# VA-Meter_Power_Supply.net
KiCad netlist of a schematic drawn in EAGLE
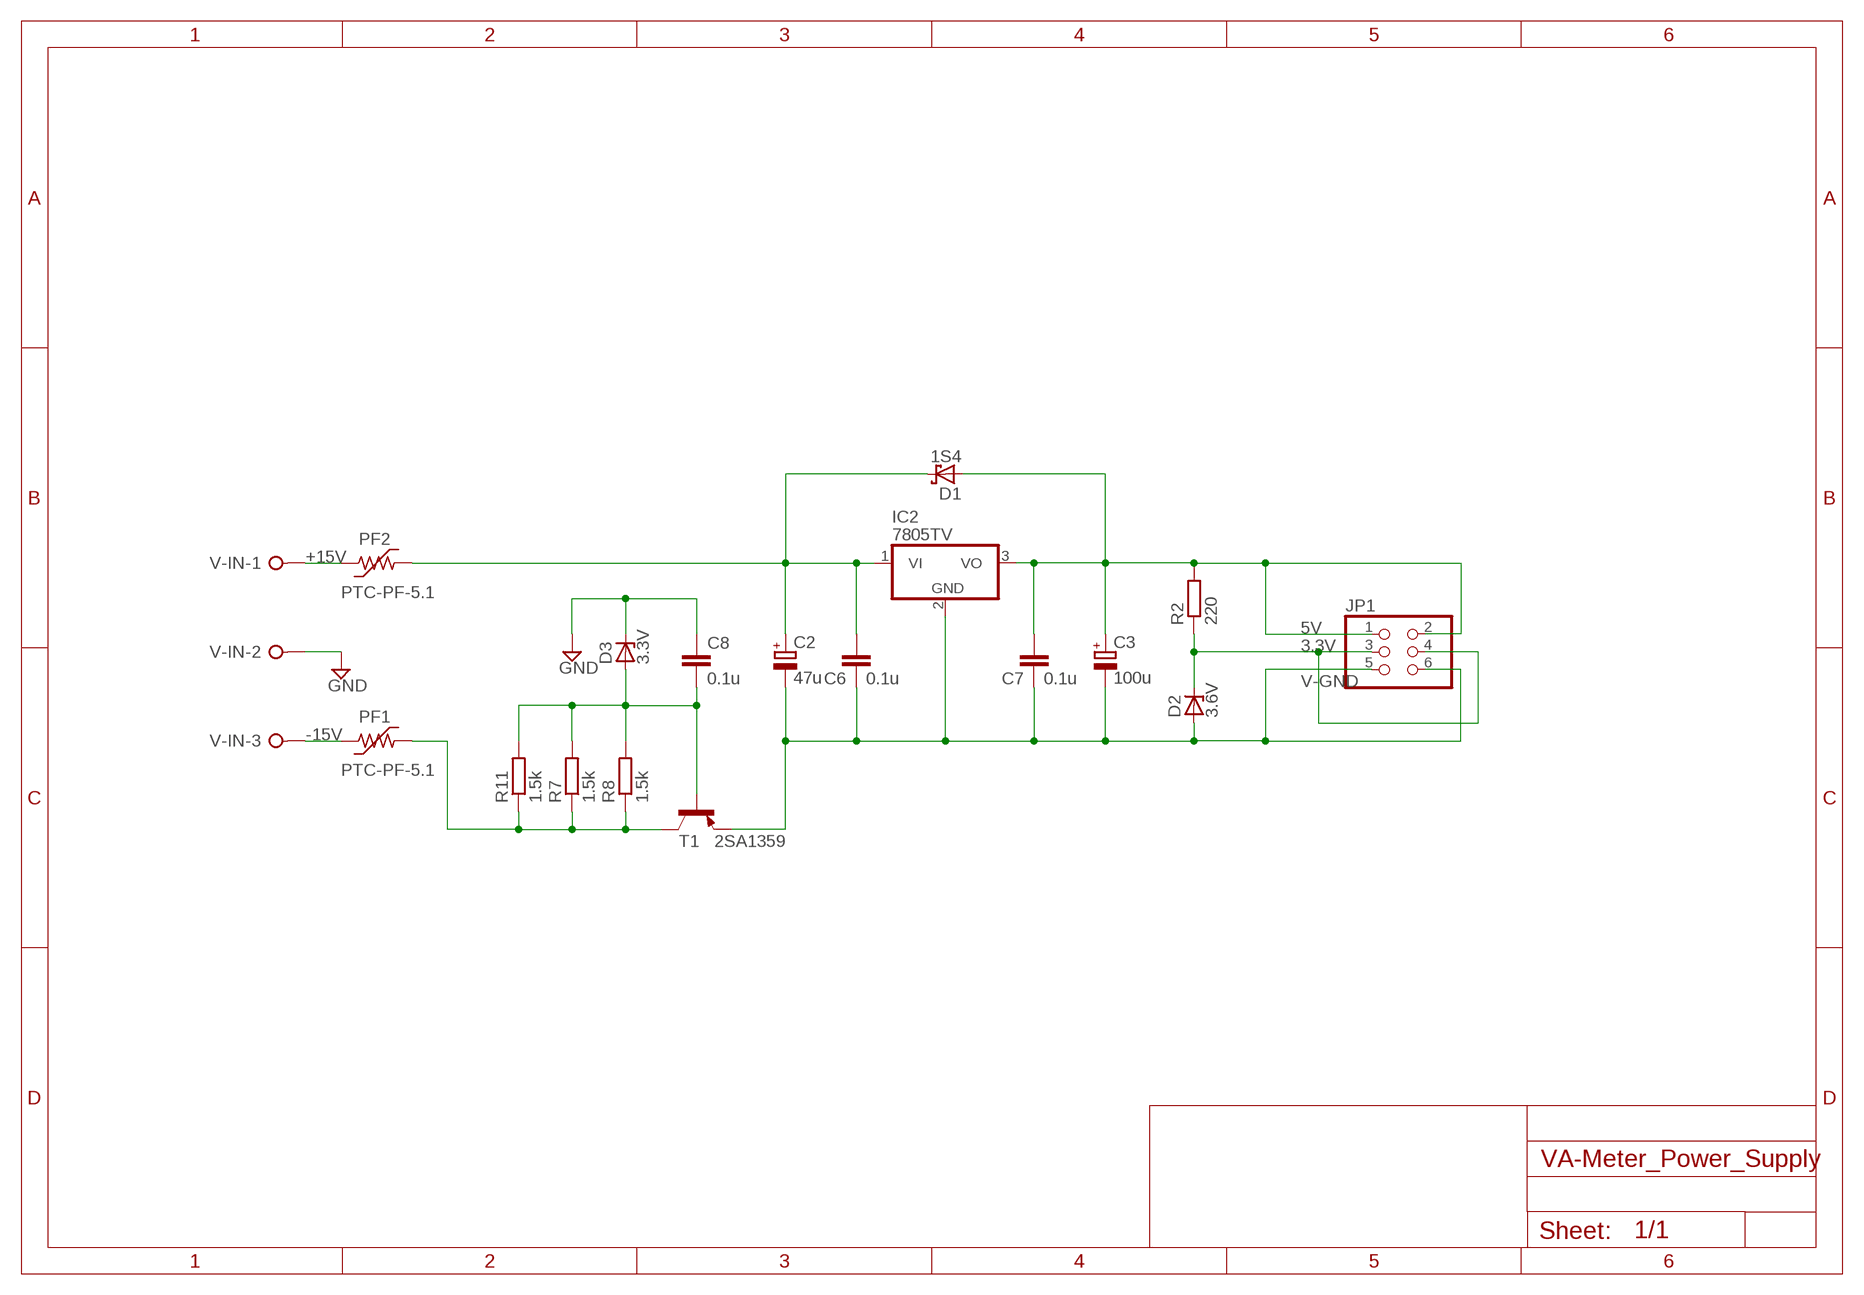
[diagram p0: schematic, sheet 1]

(export (version "E")
  (design (tool "Eeschema 10.0.6"))
  (components
    (comp (ref "C2")
      (value "47u")
      (footprint "eagle-import:E2,5-5")
      (libsource (lib "eagle-import") (part "CPOL-EUE2.5-5"))
    )
    (comp (ref "C3")
      (value "100u")
      (footprint "eagle-import:E2,5-6")
      (libsource (lib "eagle-import") (part "CPOL-EUE2.5-6"))
    )
    (comp (ref "C6")
      (value "0.1u")
      (footprint "eagle-import:C050-024X044")
      (libsource (lib "eagle-import") (part "C-EU050-024X044"))
    )
    (comp (ref "C7")
      (value "0.1u")
      (footprint "eagle-import:C050-024X044")
      (libsource (lib "eagle-import") (part "C-EU050-024X044"))
    )
    (comp (ref "C8")
      (value "0.1u")
      (footprint "eagle-import:C050-024X044")
      (libsource (lib "eagle-import") (part "C-EU050-024X044"))
    )
    (comp (ref "D1")
      (value "1S4")
      (footprint "eagle-import:DO35-7")
      (libsource (lib "eagle-import") (part "SCHOTTKY-DIODEDO35-7"))
    )
    (comp (ref "D2")
      (value "3.6V")
      (footprint "eagle-import:ZDIO-5")
      (libsource (lib "eagle-import") (part "ZENER-DIODEZD-5"))
    )
    (comp (ref "D3")
      (value "3.3V")
      (footprint "eagle-import:ZDIO-5")
      (libsource (lib "eagle-import") (part "ZENER-DIODEZD-5"))
    )
    (comp (ref "IC2")
      (value "7805TV")
      (footprint "eagle-import:TO220V")
      (libsource (lib "eagle-import") (part "78TV05"))
    )
    (comp (ref "JP1")
      (value "PINHD-2X3")
      (footprint "eagle-import:2X03")
      (libsource (lib "eagle-import") (part "PINHD-2X3"))
    )
    (comp (ref "PF1")
      (value "PTC-PF-5.1")
      (footprint "eagle-import:PF-5.1")
      (libsource (lib "eagle-import") (part "PTC-PF-5.1"))
    )
    (comp (ref "PF2")
      (value "PTC-PF-5.1")
      (footprint "eagle-import:PF-5.1")
      (libsource (lib "eagle-import") (part "PTC-PF-5.1"))
    )
    (comp (ref "R2")
      (value "220")
      (footprint "eagle-import:0204_7")
      (libsource (lib "eagle-import") (part "R-EU_0204/7"))
    )
    (comp (ref "R7")
      (value "1.5k")
      (footprint "eagle-import:0207_7")
      (libsource (lib "eagle-import") (part "R-EU_0207/7"))
    )
    (comp (ref "R8")
      (value "1.5k")
      (footprint "eagle-import:0207_7")
      (libsource (lib "eagle-import") (part "R-EU_0207/7"))
    )
    (comp (ref "R11")
      (value "1.5k")
      (footprint "eagle-import:0207_7")
      (libsource (lib "eagle-import") (part "R-EU_0207/7"))
    )
    (comp (ref "T1")
      (value "2SA1359")
      (footprint "eagle-import:TO126V")
      (libsource (lib "eagle-import") (part "-PNP-TO126V"))
    )
    (comp (ref "V-IN")
      (value "W237-03P")
      (footprint "eagle-import:W237-133")
      (libsource (lib "eagle-import") (part "W237-03P"))
    )
  )
  (nets
    (net (code "1") (name "/+15V") (class "Default")
      (node (ref "C2") (pin "+") (pinfunction "+_+") (pintype "passive"))
      (node (ref "C6") (pin "2") (pinfunction "2_2") (pintype "passive"))
      (node (ref "D1") (pin "C") (pinfunction "C_C") (pintype "passive"))
      (node (ref "IC2") (pin "1") (pinfunction "VI_1") (pintype "input"))
      (node (ref "PF2") (pin "2") (pinfunction "2_2") (pintype "passive"))
    )
    (net (code "2") (name "/-15V") (class "Default")
      (node (ref "PF1") (pin "2") (pinfunction "2_2") (pintype "passive"))
      (node (ref "R11") (pin "1") (pinfunction "1_1") (pintype "passive"))
      (node (ref "R7") (pin "1") (pinfunction "1_1") (pintype "passive"))
      (node (ref "R8") (pin "1") (pinfunction "1_1") (pintype "passive"))
      (node (ref "T1") (pin "2") (pinfunction "C_2") (pintype "passive"))
    )
    (net (code "3") (name "/3.3V") (class "Default")
      (node (ref "D2") (pin "C") (pinfunction "C_C") (pintype "passive"))
      (node (ref "JP1") (pin "3") (pinfunction "3_3") (pintype "passive"))
      (node (ref "JP1") (pin "4") (pinfunction "4_4") (pintype "passive"))
      (node (ref "R2") (pin "1") (pinfunction "1_1") (pintype "passive"))
    )
    (net (code "4") (name "/5V") (class "Default")
      (node (ref "C3") (pin "+") (pinfunction "+_+") (pintype "passive"))
      (node (ref "C7") (pin "2") (pinfunction "2_2") (pintype "passive"))
      (node (ref "D1") (pin "A") (pinfunction "A_A") (pintype "passive"))
      (node (ref "IC2") (pin "3") (pinfunction "VO_3") (pintype "passive"))
      (node (ref "JP1") (pin "1") (pinfunction "1_1") (pintype "passive"))
      (node (ref "JP1") (pin "2") (pinfunction "2_2") (pintype "passive"))
      (node (ref "R2") (pin "2") (pinfunction "2_2") (pintype "passive"))
    )
    (net (code "5") (name "/V-GND") (class "Default")
      (node (ref "C2") (pin "-") (pinfunction "-_-") (pintype "passive"))
      (node (ref "C3") (pin "-") (pinfunction "-_-") (pintype "passive"))
      (node (ref "C6") (pin "1") (pinfunction "1_1") (pintype "passive"))
      (node (ref "C7") (pin "1") (pinfunction "1_1") (pintype "passive"))
      (node (ref "D2") (pin "A") (pinfunction "A_A") (pintype "passive"))
      (node (ref "IC2") (pin "2") (pinfunction "GND_2") (pintype "passive"))
      (node (ref "JP1") (pin "5") (pinfunction "5_5") (pintype "passive"))
      (node (ref "JP1") (pin "6") (pinfunction "6_6") (pintype "passive"))
      (node (ref "T1") (pin "1") (pinfunction "E_1") (pintype "passive"))
    )
    (net (code "6") (name "GND") (class "Default")
      (node (ref "C8") (pin "1") (pinfunction "1_1") (pintype "passive"))
      (node (ref "D3") (pin "C") (pinfunction "C_C") (pintype "passive"))
      (node (ref "V-IN") (pin "2") (pinfunction "KL_2") (pintype "passive"))
    )
    (net (code "7") (name "Net-(T1-B)") (class "Default")
      (node (ref "C8") (pin "2") (pinfunction "2_2") (pintype "passive"))
      (node (ref "D3") (pin "A") (pinfunction "A_A") (pintype "passive"))
      (node (ref "R11") (pin "2") (pinfunction "2_2") (pintype "passive"))
      (node (ref "R7") (pin "2") (pinfunction "2_2") (pintype "passive"))
      (node (ref "R8") (pin "2") (pinfunction "2_2") (pintype "passive"))
      (node (ref "T1") (pin "3") (pinfunction "B_3") (pintype "passive"))
    )
    (net (code "8") (name "Net-(V-INA-KL)") (class "Default")
      (node (ref "PF2") (pin "1") (pinfunction "1_1") (pintype "passive"))
      (node (ref "V-IN") (pin "1") (pinfunction "KL_1") (pintype "passive"))
    )
    (net (code "9") (name "Net-(V-INC-KL)") (class "Default")
      (node (ref "PF1") (pin "1") (pinfunction "1_1") (pintype "passive"))
      (node (ref "V-IN") (pin "3") (pinfunction "KL_3") (pintype "passive"))
    )
  )
)
